# ShineRider.net
KiCad netlist of a schematic drawn in Altium Designer
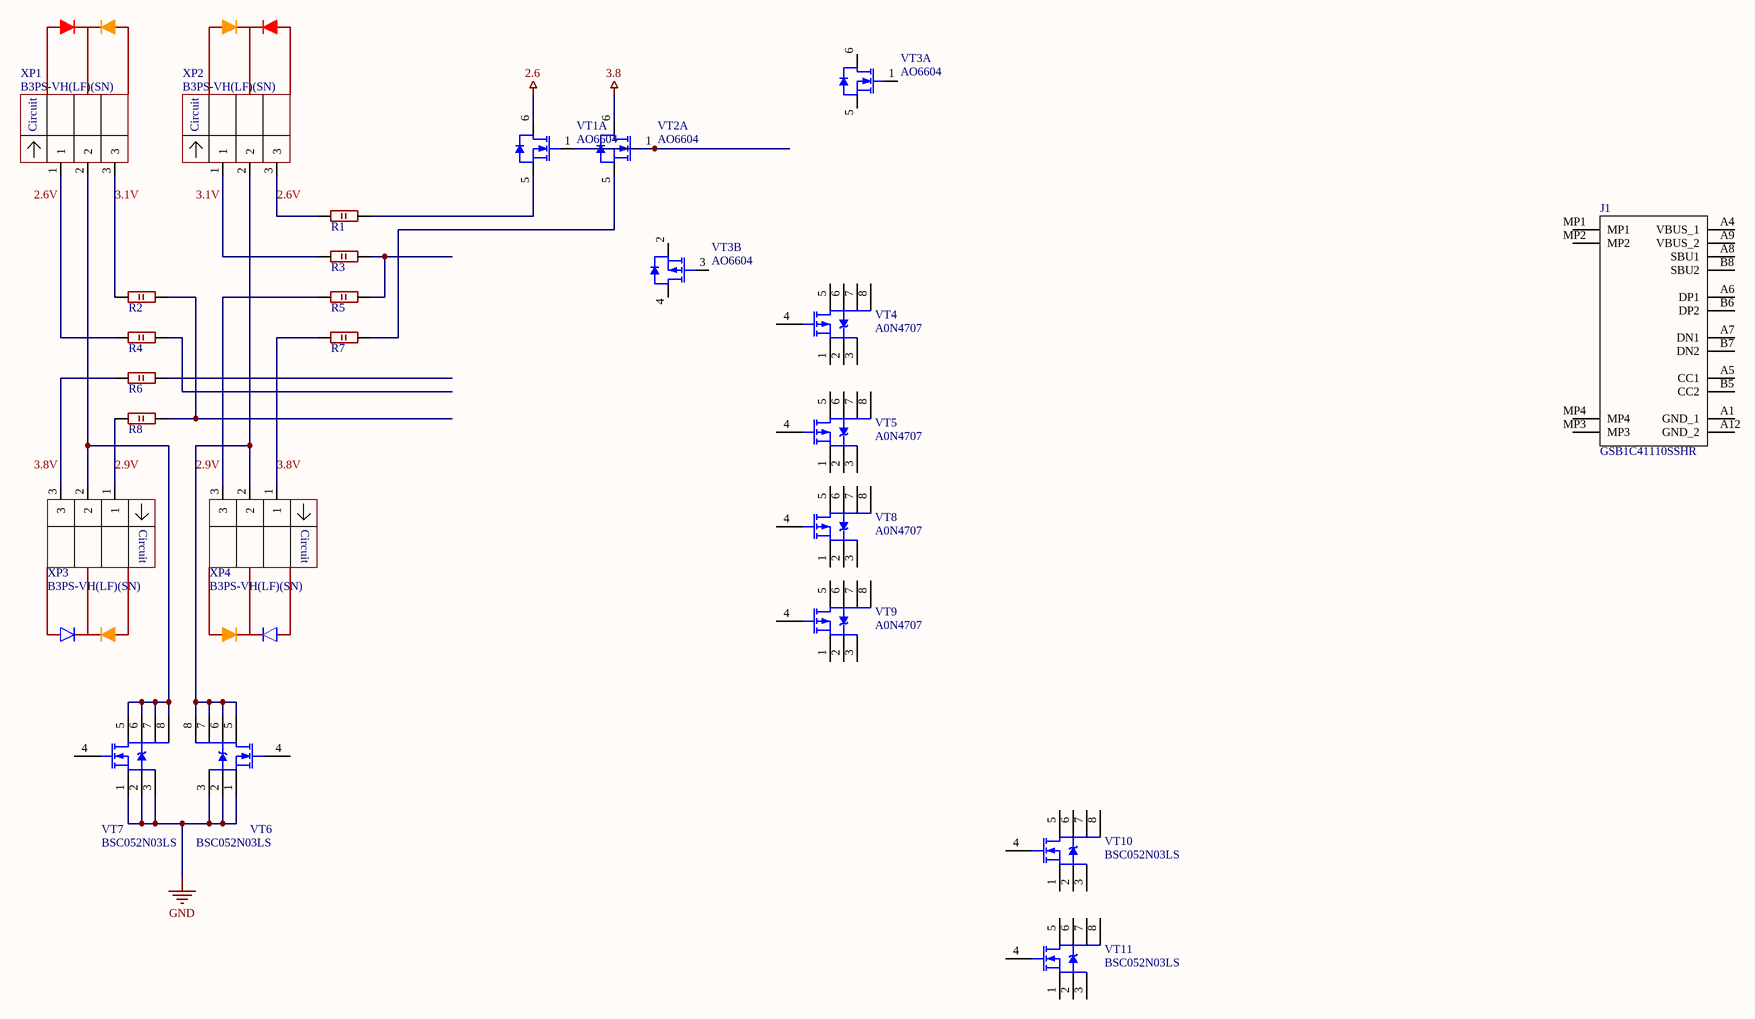
[diagram p0: ShineRider.SchDoc]

(export (version "E")
  (design (tool "Eeschema 10.0.6"))
  (components
    (comp (ref "J1")
      (value "GSB1C41110SSHR")
      (footprint "GSB1C41110SSHR")
      (fields (field (name "DIGI-KEY PART NUMBER") "664-GSB1C41110SSHRCT-ND"))
      (libsource (lib "SssAccesDatbase") (part "GSB1C41110SSHR"))
    )
    (comp (ref "R1")
      (value "0.1R 1%")
      (footprint "R2512")
      (description "100 mOhms ±1% 2W Chip Resistor 2512")
      (fields (field (name "PART NUMBER") "MFHA2512R1000FE"))
      (libsource (lib "SssAccesDatbase") (part "Resistor 2W"))
    )
    (comp (ref "R2")
      (value "0.1R 1%")
      (footprint "R2512")
      (description "100 mOhms ±1% 2W Chip Resistor 2512")
      (fields (field (name "PART NUMBER") "MFHA2512R1000FE"))
      (libsource (lib "SssAccesDatbase") (part "Resistor 2W"))
    )
    (comp (ref "R3")
      (value "0.1R 1%")
      (footprint "R2512")
      (description "100 mOhms ±1% 2W Chip Resistor 2512")
      (fields (field (name "PART NUMBER") "MFHA2512R1000FE"))
      (libsource (lib "SssAccesDatbase") (part "Resistor 2W"))
    )
    (comp (ref "R4")
      (value "0.1R 1%")
      (footprint "R2512")
      (description "100 mOhms ±1% 2W Chip Resistor 2512")
      (fields (field (name "PART NUMBER") "MFHA2512R1000FE"))
      (libsource (lib "SssAccesDatbase") (part "Resistor 2W"))
    )
    (comp (ref "R5")
      (value "0.1R 1%")
      (footprint "R2512")
      (description "100 mOhms ±1% 2W Chip Resistor 2512")
      (fields (field (name "PART NUMBER") "MFHA2512R1000FE"))
      (libsource (lib "SssAccesDatbase") (part "Resistor 2W"))
    )
    (comp (ref "R6")
      (value "0.1R 1%")
      (footprint "R2512")
      (description "100 mOhms ±1% 2W Chip Resistor 2512")
      (fields (field (name "PART NUMBER") "MFHA2512R1000FE"))
      (libsource (lib "SssAccesDatbase") (part "Resistor 2W"))
    )
    (comp (ref "R7")
      (value "0.1R 1%")
      (footprint "R2512")
      (description "100 mOhms ±1% 2W Chip Resistor 2512")
      (fields (field (name "PART NUMBER") "MFHA2512R1000FE"))
      (libsource (lib "SssAccesDatbase") (part "Resistor 2W"))
    )
    (comp (ref "R8")
      (value "0.1R 1%")
      (footprint "R2512")
      (description "100 mOhms ±1% 2W Chip Resistor 2512")
      (fields (field (name "PART NUMBER") "MFHA2512R1000FE"))
      (libsource (lib "SssAccesDatbase") (part "Resistor 2W"))
    )
    (comp (ref "VT1")
      (value "AO6604")
      (footprint "TSOP-6")
      (description "Mosfet Array N and P-Channel Complementary 20V 3.4A, 2.5A 1.1W Surface Mount 6-TSOP")
      (fields (field (name "DIGI-KEY PART NUMBER") "785-1078-1-ND"))
      (libsource (lib "SssAccesDatbase") (part "AO6604"))
    )
    (comp (ref "VT2")
      (value "AO6604")
      (footprint "TSOP-6")
      (description "Mosfet Array N and P-Channel Complementary 20V 3.4A, 2.5A 1.1W Surface Mount 6-TSOP")
      (fields (field (name "DIGI-KEY PART NUMBER") "785-1078-1-ND"))
      (libsource (lib "SssAccesDatbase") (part "AO6604"))
    )
    (comp (ref "VT3")
      (value "AO6604")
      (footprint "TSOP-6")
      (description "Mosfet Array N and P-Channel Complementary 20V 3.4A, 2.5A 1.1W Surface Mount 6-TSOP")
      (fields (field (name "DIGI-KEY PART NUMBER") "785-1078-1-ND"))
      (libsource (lib "SssAccesDatbase") (part "AO6604"))
    )
    (comp (ref "VT4")
      (value "A0N4707")
      (footprint "PG-TDSON-8")
      (description "P-Channel 20V 14.5A (Ta), 40A (Tc) 3.1W (Ta), 29W (Tc) Surface Mount 8-DFN (3x3)")
      (libsource (lib "SssAccesDatbase") (part "A0N7407"))
    )
    (comp (ref "VT5")
      (value "A0N4707")
      (footprint "PG-TDSON-8")
      (description "P-Channel 20V 14.5A (Ta), 40A (Tc) 3.1W (Ta), 29W (Tc) Surface Mount 8-DFN (3x3)")
      (libsource (lib "SssAccesDatbase") (part "A0N7407"))
    )
    (comp (ref "VT6")
      (value "BSC052N03LS")
      (footprint "PG-TDSON-8")
      (libsource (lib "SssAccesDatbase") (part "BSC052N03LS"))
    )
    (comp (ref "VT7")
      (value "BSC052N03LS")
      (footprint "PG-TDSON-8")
      (libsource (lib "SssAccesDatbase") (part "BSC052N03LS"))
    )
    (comp (ref "VT8")
      (value "A0N4707")
      (footprint "PG-TDSON-8")
      (description "P-Channel 20V 14.5A (Ta), 40A (Tc) 3.1W (Ta), 29W (Tc) Surface Mount 8-DFN (3x3)")
      (libsource (lib "SssAccesDatbase") (part "A0N7407"))
    )
    (comp (ref "VT9")
      (value "A0N4707")
      (footprint "PG-TDSON-8")
      (description "P-Channel 20V 14.5A (Ta), 40A (Tc) 3.1W (Ta), 29W (Tc) Surface Mount 8-DFN (3x3)")
      (libsource (lib "SssAccesDatbase") (part "A0N7407"))
    )
    (comp (ref "VT10")
      (value "BSC052N03LS")
      (footprint "PG-TDSON-8")
      (libsource (lib "SssAccesDatbase") (part "BSC052N03LS"))
    )
    (comp (ref "VT11")
      (value "BSC052N03LS")
      (footprint "PG-TDSON-8")
      (libsource (lib "SssAccesDatbase") (part "BSC052N03LS"))
    )
    (comp (ref "XP1")
      (value "B3PS-VH(LF)(SN)")
      (footprint "B3PS-VH(LF)(SN)")
      (description "CONN HEADER VH SIDE 3POS 3.96MM")
      (libsource (lib "") (part "XP-3_1"))
    )
    (comp (ref "XP2")
      (value "B3PS-VH(LF)(SN)")
      (footprint "B3PS-VH(LF)(SN)")
      (description "CONN HEADER VH SIDE 3POS 3.96MM")
      (libsource (lib "") (part "XP-3_1"))
    )
    (comp (ref "XP3")
      (value "B3PS-VH(LF)(SN)")
      (footprint "B3PS-VH(LF)(SN)")
      (description "CONN HEADER VH SIDE 3POS 3.96MM")
      (libsource (lib "SssAccesDatbase") (part "XP-3"))
    )
    (comp (ref "XP4")
      (value "B3PS-VH(LF)(SN)")
      (footprint "B3PS-VH(LF)(SN)")
      (description "CONN HEADER VH SIDE 3POS 3.96MM")
      (libsource (lib "SssAccesDatbase") (part "XP-3"))
    )
  )
  (nets
    (net (code "1") (name "2.6") (class "Default")
      (node (ref "VT1") (pin "6") (pinfunction "D1_6") (pintype "passive"))
    )
    (net (code "2") (name "3.8") (class "Default")
      (node (ref "VT2") (pin "6") (pinfunction "D1_6") (pintype "passive"))
    )
    (net (code "3") (name "GND") (class "Default")
      (node (ref "VT6") (pin "1") (pinfunction "S1_1") (pintype "passive"))
      (node (ref "VT6") (pin "2") (pinfunction "S2_2") (pintype "passive"))
      (node (ref "VT6") (pin "3") (pinfunction "S3_3") (pintype "passive"))
      (node (ref "VT7") (pin "1") (pinfunction "S1_1") (pintype "passive"))
      (node (ref "VT7") (pin "2") (pinfunction "S2_2") (pintype "passive"))
      (node (ref "VT7") (pin "3") (pinfunction "S3_3") (pintype "passive"))
    )
    (net (code "4") (name "Net-(R1-Pad1)") (class "Default")
      (node (ref "R1") (pin "1") (pinfunction "1_1") (pintype "passive"))
      (node (ref "XP2") (pin "3") (pinfunction "3_3") (pintype "passive"))
    )
    (net (code "5") (name "Net-(R2-Pad1)") (class "Default")
      (node (ref "R2") (pin "1") (pinfunction "1_1") (pintype "passive"))
      (node (ref "XP1") (pin "3") (pinfunction "3_3") (pintype "passive"))
    )
    (net (code "6") (name "Net-(R2-Pad2)") (class "Default")
      (node (ref "R2") (pin "2") (pinfunction "2_2") (pintype "passive"))
      (node (ref "R8") (pin "2") (pinfunction "2_2") (pintype "passive"))
    )
    (net (code "7") (name "Net-(R3-Pad1)") (class "Default")
      (node (ref "R3") (pin "1") (pinfunction "1_1") (pintype "passive"))
      (node (ref "XP2") (pin "1") (pinfunction "1_1") (pintype "passive"))
    )
    (net (code "8") (name "Net-(R3-Pad2)") (class "Default")
      (node (ref "R3") (pin "2") (pinfunction "2_2") (pintype "passive"))
      (node (ref "R5") (pin "2") (pinfunction "2_2") (pintype "passive"))
    )
    (net (code "9") (name "Net-(R4-Pad1)") (class "Default")
      (node (ref "R4") (pin "1") (pinfunction "1_1") (pintype "passive"))
      (node (ref "XP1") (pin "1") (pinfunction "1_1") (pintype "passive"))
    )
    (net (code "10") (name "Net-(R5-Pad1)") (class "Default")
      (node (ref "R5") (pin "1") (pinfunction "1_1") (pintype "passive"))
      (node (ref "XP4") (pin "3") (pinfunction "3_3") (pintype "passive"))
    )
    (net (code "11") (name "Net-(R6-Pad1)") (class "Default")
      (node (ref "R6") (pin "1") (pinfunction "1_1") (pintype "passive"))
      (node (ref "XP3") (pin "3") (pinfunction "3_3") (pintype "passive"))
    )
    (net (code "12") (name "Net-(R7-Pad1)") (class "Default")
      (node (ref "R7") (pin "1") (pinfunction "1_1") (pintype "passive"))
      (node (ref "XP4") (pin "1") (pinfunction "1_1") (pintype "passive"))
    )
    (net (code "13") (name "Net-(R8-Pad1)") (class "Default")
      (node (ref "R8") (pin "1") (pinfunction "1_1") (pintype "passive"))
      (node (ref "XP3") (pin "1") (pinfunction "1_1") (pintype "passive"))
    )
    (net (code "14") (name "Net-(VT1A-G1)") (class "Default")
      (node (ref "VT1") (pin "1") (pinfunction "G1_1") (pintype "passive"))
      (node (ref "VT2") (pin "1") (pinfunction "G1_1") (pintype "passive"))
    )
    (net (code "15") (name "Net-(VT1A-S1)") (class "Default")
      (node (ref "R1") (pin "2") (pinfunction "2_2") (pintype "passive"))
      (node (ref "VT1") (pin "5") (pinfunction "S1_5") (pintype "passive"))
    )
    (net (code "16") (name "Net-(VT2A-S1)") (class "Default")
      (node (ref "R7") (pin "2") (pinfunction "2_2") (pintype "passive"))
      (node (ref "VT2") (pin "5") (pinfunction "S1_5") (pintype "passive"))
    )
    (net (code "17") (name "Net-(VT6-D7)") (class "Default")
      (node (ref "VT6") (pin "5") (pinfunction "D6_5") (pintype "passive"))
      (node (ref "VT6") (pin "6") (pinfunction "D6_6") (pintype "passive"))
      (node (ref "VT6") (pin "7") (pinfunction "D7_7") (pintype "passive"))
      (node (ref "VT6") (pin "8") (pinfunction "D8_8") (pintype "passive"))
      (node (ref "XP2") (pin "2") (pinfunction "2_2") (pintype "passive"))
      (node (ref "XP4") (pin "2") (pinfunction "2_2") (pintype "passive"))
    )
    (net (code "18") (name "Net-(VT7-D7)") (class "Default")
      (node (ref "VT7") (pin "5") (pinfunction "D6_5") (pintype "passive"))
      (node (ref "VT7") (pin "6") (pinfunction "D6_6") (pintype "passive"))
      (node (ref "VT7") (pin "7") (pinfunction "D7_7") (pintype "passive"))
      (node (ref "VT7") (pin "8") (pinfunction "D8_8") (pintype "passive"))
      (node (ref "XP1") (pin "2") (pinfunction "2_2") (pintype "passive"))
      (node (ref "XP3") (pin "2") (pinfunction "2_2") (pintype "passive"))
    )
    (net (code "19") (name "unconnected-(J1-CC1-PadA5)") (class "Default")
      (node (ref "J1") (pin "A5") (pinfunction "CC1_A5") (pintype "passive"))
    )
    (net (code "20") (name "unconnected-(J1-CC2-PadB5)") (class "Default")
      (node (ref "J1") (pin "B5") (pinfunction "CC2_B5") (pintype "passive"))
    )
    (net (code "21") (name "unconnected-(J1-DN1-PadA7)") (class "Default")
      (node (ref "J1") (pin "A7") (pinfunction "DN1_A7") (pintype "passive"))
    )
    (net (code "22") (name "unconnected-(J1-DN2-PadB7)") (class "Default")
      (node (ref "J1") (pin "B7") (pinfunction "DN2_B7") (pintype "passive"))
    )
    (net (code "23") (name "unconnected-(J1-DP1-PadA6)") (class "Default")
      (node (ref "J1") (pin "A6") (pinfunction "DP1_A6") (pintype "passive"))
    )
    (net (code "24") (name "unconnected-(J1-DP2-PadB6)") (class "Default")
      (node (ref "J1") (pin "B6") (pinfunction "DP2_B6") (pintype "passive"))
    )
    (net (code "25") (name "unconnected-(J1-GND_1-PadA1)") (class "Default")
      (node (ref "J1") (pin "A1") (pinfunction "GND_1_A1") (pintype "passive"))
    )
    (net (code "26") (name "unconnected-(J1-GND_2-PadA12)") (class "Default")
      (node (ref "J1") (pin "A12") (pinfunction "GND_2_A12") (pintype "passive"))
    )
    (net (code "27") (name "unconnected-(J1-PadMP1)") (class "Default")
      (node (ref "J1") (pin "MP1") (pinfunction "MP1_MP1") (pintype "passive"))
    )
    (net (code "28") (name "unconnected-(J1-PadMP2)") (class "Default")
      (node (ref "J1") (pin "MP2") (pinfunction "MP2_MP2") (pintype "passive"))
    )
    (net (code "29") (name "unconnected-(J1-PadMP3)") (class "Default")
      (node (ref "J1") (pin "MP3") (pinfunction "MP3_MP3") (pintype "passive"))
    )
    (net (code "30") (name "unconnected-(J1-PadMP4)") (class "Default")
      (node (ref "J1") (pin "MP4") (pinfunction "MP4_MP4") (pintype "passive"))
    )
    (net (code "31") (name "unconnected-(J1-SBU1-PadA8)") (class "Default")
      (node (ref "J1") (pin "A8") (pinfunction "SBU1_A8") (pintype "passive"))
    )
    (net (code "32") (name "unconnected-(J1-SBU2-PadB8)") (class "Default")
      (node (ref "J1") (pin "B8") (pinfunction "SBU2_B8") (pintype "passive"))
    )
    (net (code "33") (name "unconnected-(J1-VBUS_1-PadA4)") (class "Default")
      (node (ref "J1") (pin "A4") (pinfunction "VBUS_1_A4") (pintype "passive"))
    )
    (net (code "34") (name "unconnected-(J1-VBUS_2-PadA9)") (class "Default")
      (node (ref "J1") (pin "A9") (pinfunction "VBUS_2_A9") (pintype "passive"))
    )
    (net (code "35") (name "unconnected-(R4-Pad2)") (class "Default")
      (node (ref "R4") (pin "2") (pinfunction "2_2") (pintype "passive"))
    )
    (net (code "36") (name "unconnected-(R6-Pad2)") (class "Default")
      (node (ref "R6") (pin "2") (pinfunction "2_2") (pintype "passive"))
    )
    (net (code "37") (name "unconnected-(VT3A-D1-Pad6)") (class "Default")
      (node (ref "VT3") (pin "6") (pinfunction "D1_6") (pintype "passive"))
    )
    (net (code "38") (name "unconnected-(VT3A-G1-Pad1)") (class "Default")
      (node (ref "VT3") (pin "1") (pinfunction "G1_1") (pintype "passive"))
    )
    (net (code "39") (name "unconnected-(VT3A-S1-Pad5)") (class "Default")
      (node (ref "VT3") (pin "5") (pinfunction "S1_5") (pintype "passive"))
    )
    (net (code "40") (name "unconnected-(VT3B-D2-Pad4)") (class "Default")
      (node (ref "VT3") (pin "4") (pinfunction "D2_4") (pintype "passive"))
    )
    (net (code "41") (name "unconnected-(VT3B-G2-Pad3)") (class "Default")
      (node (ref "VT3") (pin "3") (pinfunction "G2_3") (pintype "passive"))
    )
    (net (code "42") (name "unconnected-(VT3B-S2-Pad2)") (class "Default")
      (node (ref "VT3") (pin "2") (pinfunction "S2_2") (pintype "passive"))
    )
    (net (code "43") (name "unconnected-(VT4-D6-Pad5)") (class "Default")
      (node (ref "VT4") (pin "5") (pinfunction "D6_5") (pintype "passive"))
    )
    (net (code "44") (name "unconnected-(VT4-D6-Pad6)") (class "Default")
      (node (ref "VT4") (pin "6") (pinfunction "D6_6") (pintype "passive"))
    )
    (net (code "45") (name "unconnected-(VT4-D7-Pad7)") (class "Default")
      (node (ref "VT4") (pin "7") (pinfunction "D7_7") (pintype "passive"))
    )
    (net (code "46") (name "unconnected-(VT4-D8-Pad8)") (class "Default")
      (node (ref "VT4") (pin "8") (pinfunction "D8_8") (pintype "passive"))
    )
    (net (code "47") (name "unconnected-(VT4-G-Pad4)") (class "Default")
      (node (ref "VT4") (pin "4") (pinfunction "G_4") (pintype "passive"))
    )
    (net (code "48") (name "unconnected-(VT4-S1-Pad1)") (class "Default")
      (node (ref "VT4") (pin "1") (pinfunction "S1_1") (pintype "passive"))
    )
    (net (code "49") (name "unconnected-(VT4-S2-Pad2)") (class "Default")
      (node (ref "VT4") (pin "2") (pinfunction "S2_2") (pintype "passive"))
    )
    (net (code "50") (name "unconnected-(VT4-S3-Pad3)") (class "Default")
      (node (ref "VT4") (pin "3") (pinfunction "S3_3") (pintype "passive"))
    )
    (net (code "51") (name "unconnected-(VT5-D6-Pad5)") (class "Default")
      (node (ref "VT5") (pin "5") (pinfunction "D6_5") (pintype "passive"))
    )
    (net (code "52") (name "unconnected-(VT5-D6-Pad6)") (class "Default")
      (node (ref "VT5") (pin "6") (pinfunction "D6_6") (pintype "passive"))
    )
    (net (code "53") (name "unconnected-(VT5-D7-Pad7)") (class "Default")
      (node (ref "VT5") (pin "7") (pinfunction "D7_7") (pintype "passive"))
    )
    (net (code "54") (name "unconnected-(VT5-D8-Pad8)") (class "Default")
      (node (ref "VT5") (pin "8") (pinfunction "D8_8") (pintype "passive"))
    )
    (net (code "55") (name "unconnected-(VT5-G-Pad4)") (class "Default")
      (node (ref "VT5") (pin "4") (pinfunction "G_4") (pintype "passive"))
    )
    (net (code "56") (name "unconnected-(VT5-S1-Pad1)") (class "Default")
      (node (ref "VT5") (pin "1") (pinfunction "S1_1") (pintype "passive"))
    )
    (net (code "57") (name "unconnected-(VT5-S2-Pad2)") (class "Default")
      (node (ref "VT5") (pin "2") (pinfunction "S2_2") (pintype "passive"))
    )
    (net (code "58") (name "unconnected-(VT5-S3-Pad3)") (class "Default")
      (node (ref "VT5") (pin "3") (pinfunction "S3_3") (pintype "passive"))
    )
    (net (code "59") (name "unconnected-(VT6-G-Pad4)") (class "Default")
      (node (ref "VT6") (pin "4") (pinfunction "G_4") (pintype "passive"))
    )
    (net (code "60") (name "unconnected-(VT7-G-Pad4)") (class "Default")
      (node (ref "VT7") (pin "4") (pinfunction "G_4") (pintype "passive"))
    )
    (net (code "61") (name "unconnected-(VT8-D6-Pad5)") (class "Default")
      (node (ref "VT8") (pin "5") (pinfunction "D6_5") (pintype "passive"))
    )
    (net (code "62") (name "unconnected-(VT8-D6-Pad6)") (class "Default")
      (node (ref "VT8") (pin "6") (pinfunction "D6_6") (pintype "passive"))
    )
    (net (code "63") (name "unconnected-(VT8-D7-Pad7)") (class "Default")
      (node (ref "VT8") (pin "7") (pinfunction "D7_7") (pintype "passive"))
    )
    (net (code "64") (name "unconnected-(VT8-D8-Pad8)") (class "Default")
      (node (ref "VT8") (pin "8") (pinfunction "D8_8") (pintype "passive"))
    )
    (net (code "65") (name "unconnected-(VT8-G-Pad4)") (class "Default")
      (node (ref "VT8") (pin "4") (pinfunction "G_4") (pintype "passive"))
    )
    (net (code "66") (name "unconnected-(VT8-S1-Pad1)") (class "Default")
      (node (ref "VT8") (pin "1") (pinfunction "S1_1") (pintype "passive"))
    )
    (net (code "67") (name "unconnected-(VT8-S2-Pad2)") (class "Default")
      (node (ref "VT8") (pin "2") (pinfunction "S2_2") (pintype "passive"))
    )
    (net (code "68") (name "unconnected-(VT8-S3-Pad3)") (class "Default")
      (node (ref "VT8") (pin "3") (pinfunction "S3_3") (pintype "passive"))
    )
    (net (code "69") (name "unconnected-(VT9-D6-Pad5)") (class "Default")
      (node (ref "VT9") (pin "5") (pinfunction "D6_5") (pintype "passive"))
    )
    (net (code "70") (name "unconnected-(VT9-D6-Pad6)") (class "Default")
      (node (ref "VT9") (pin "6") (pinfunction "D6_6") (pintype "passive"))
    )
    (net (code "71") (name "unconnected-(VT9-D7-Pad7)") (class "Default")
      (node (ref "VT9") (pin "7") (pinfunction "D7_7") (pintype "passive"))
    )
    (net (code "72") (name "unconnected-(VT9-D8-Pad8)") (class "Default")
      (node (ref "VT9") (pin "8") (pinfunction "D8_8") (pintype "passive"))
    )
    (net (code "73") (name "unconnected-(VT9-G-Pad4)") (class "Default")
      (node (ref "VT9") (pin "4") (pinfunction "G_4") (pintype "passive"))
    )
    (net (code "74") (name "unconnected-(VT9-S1-Pad1)") (class "Default")
      (node (ref "VT9") (pin "1") (pinfunction "S1_1") (pintype "passive"))
    )
    (net (code "75") (name "unconnected-(VT9-S2-Pad2)") (class "Default")
      (node (ref "VT9") (pin "2") (pinfunction "S2_2") (pintype "passive"))
    )
    (net (code "76") (name "unconnected-(VT9-S3-Pad3)") (class "Default")
      (node (ref "VT9") (pin "3") (pinfunction "S3_3") (pintype "passive"))
    )
    (net (code "77") (name "unconnected-(VT10-D6-Pad5)") (class "Default")
      (node (ref "VT10") (pin "5") (pinfunction "D6_5") (pintype "passive"))
    )
    (net (code "78") (name "unconnected-(VT10-D6-Pad6)") (class "Default")
      (node (ref "VT10") (pin "6") (pinfunction "D6_6") (pintype "passive"))
    )
    (net (code "79") (name "unconnected-(VT10-D7-Pad7)") (class "Default")
      (node (ref "VT10") (pin "7") (pinfunction "D7_7") (pintype "passive"))
    )
    (net (code "80") (name "unconnected-(VT10-D8-Pad8)") (class "Default")
      (node (ref "VT10") (pin "8") (pinfunction "D8_8") (pintype "passive"))
    )
    (net (code "81") (name "unconnected-(VT10-G-Pad4)") (class "Default")
      (node (ref "VT10") (pin "4") (pinfunction "G_4") (pintype "passive"))
    )
    (net (code "82") (name "unconnected-(VT10-S1-Pad1)") (class "Default")
      (node (ref "VT10") (pin "1") (pinfunction "S1_1") (pintype "passive"))
    )
    (net (code "83") (name "unconnected-(VT10-S2-Pad2)") (class "Default")
      (node (ref "VT10") (pin "2") (pinfunction "S2_2") (pintype "passive"))
    )
    (net (code "84") (name "unconnected-(VT10-S3-Pad3)") (class "Default")
      (node (ref "VT10") (pin "3") (pinfunction "S3_3") (pintype "passive"))
    )
    (net (code "85") (name "unconnected-(VT11-D6-Pad5)") (class "Default")
      (node (ref "VT11") (pin "5") (pinfunction "D6_5") (pintype "passive"))
    )
    (net (code "86") (name "unconnected-(VT11-D6-Pad6)") (class "Default")
      (node (ref "VT11") (pin "6") (pinfunction "D6_6") (pintype "passive"))
    )
    (net (code "87") (name "unconnected-(VT11-D7-Pad7)") (class "Default")
      (node (ref "VT11") (pin "7") (pinfunction "D7_7") (pintype "passive"))
    )
    (net (code "88") (name "unconnected-(VT11-D8-Pad8)") (class "Default")
      (node (ref "VT11") (pin "8") (pinfunction "D8_8") (pintype "passive"))
    )
    (net (code "89") (name "unconnected-(VT11-G-Pad4)") (class "Default")
      (node (ref "VT11") (pin "4") (pinfunction "G_4") (pintype "passive"))
    )
    (net (code "90") (name "unconnected-(VT11-S1-Pad1)") (class "Default")
      (node (ref "VT11") (pin "1") (pinfunction "S1_1") (pintype "passive"))
    )
    (net (code "91") (name "unconnected-(VT11-S2-Pad2)") (class "Default")
      (node (ref "VT11") (pin "2") (pinfunction "S2_2") (pintype "passive"))
    )
    (net (code "92") (name "unconnected-(VT11-S3-Pad3)") (class "Default")
      (node (ref "VT11") (pin "3") (pinfunction "S3_3") (pintype "passive"))
    )
  )
)
